# Shield.net
KiCad netlist of a schematic drawn in Altium Designer
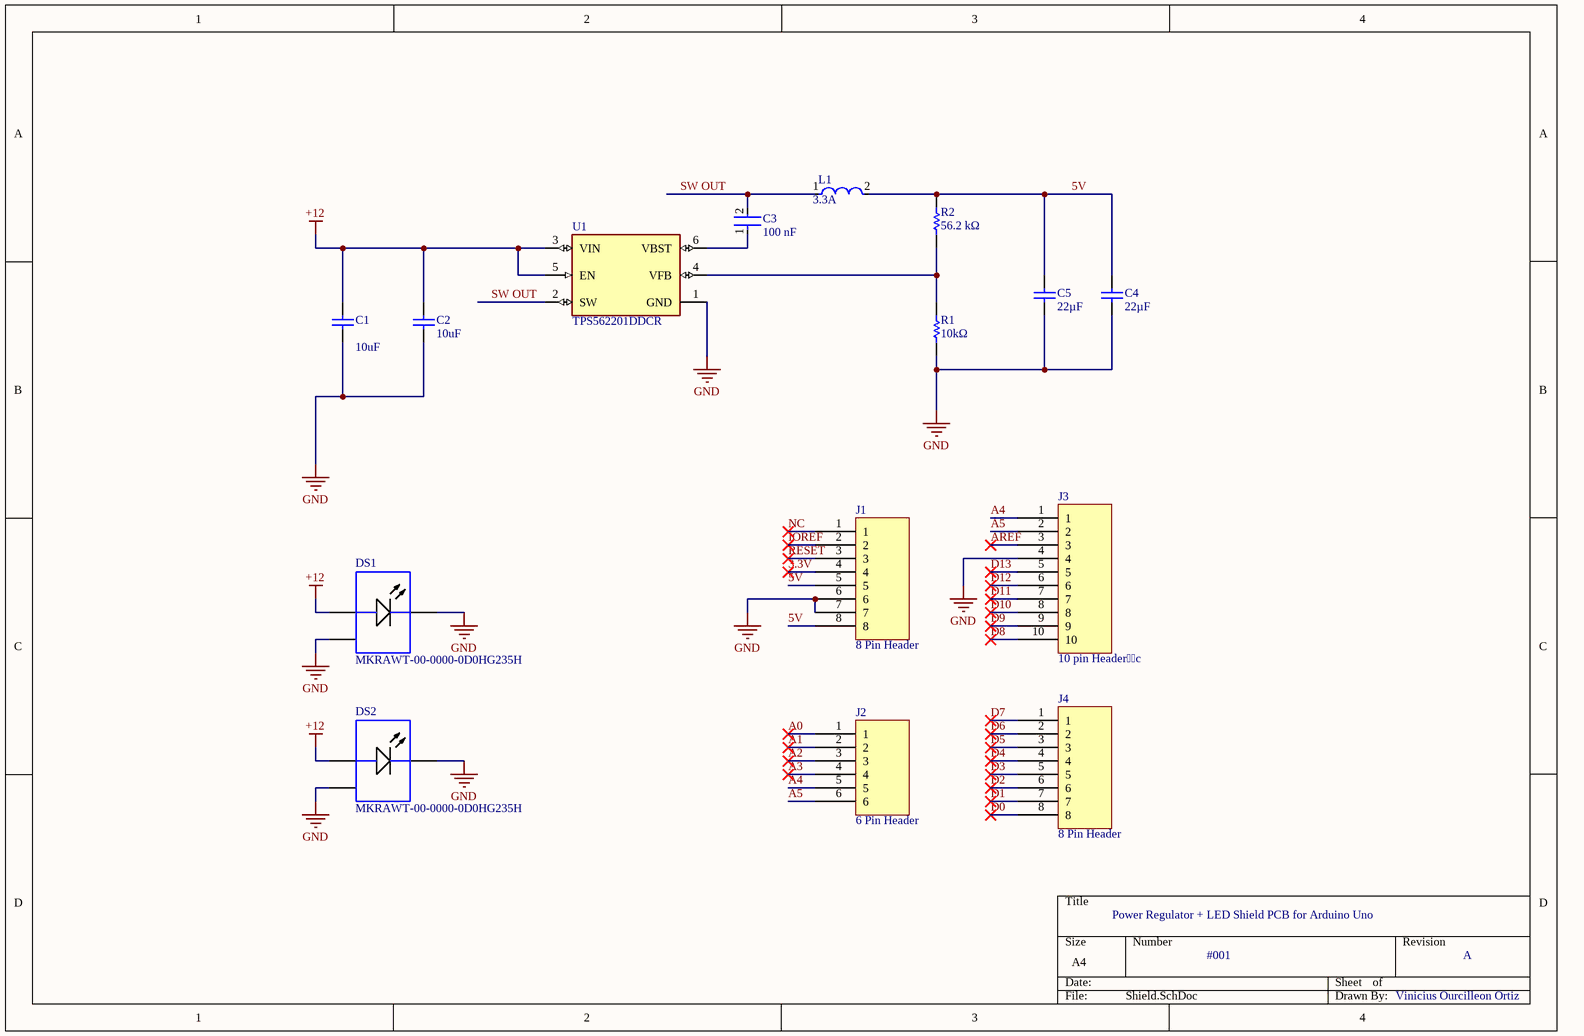
[diagram p0: Shield.SchDoc]

(export (version "E")
  (design (tool "Eeschema 10.0.6"))
  (components
    (comp (ref "C1")
      (value "GRM31CR61E106KA12L")
      (footprint "CAPC3216X180X55ML20T25")
      (description "Chip Capacitor, 10 uF, +/- 10%, 25 V, -55 to 85 degC, 1206 (3216 Metric), RoHS, Tape and Reel")
      (fields
        (field (name "MANUFACTURER") "Murata")
        (field (name "TOLERANCE") "10%")
        (field (name "CAPACITANCE") "10uF")
      )
      (libsource (lib "Altium Content Vault") (part "CAP-NP-2"))
    )
    (comp (ref "C2")
      (value "GRM31CR61E106KA12L")
      (footprint "CAPC3216X180X55ML20T25")
      (description "Chip Capacitor, 10 uF, +/- 10%, 25 V, -55 to 85 degC, 1206 (3216 Metric), RoHS, Tape and Reel")
      (fields
        (field (name "MANUFACTURER") "Murata")
        (field (name "TOLERANCE") "10%")
        (field (name "CAPACITANCE") "10uF")
      )
      (libsource (lib "Altium Content Vault") (part "CAP-NP-2"))
    )
    (comp (ref "C3")
      (value "CC0805KRX7R8BB104")
      (footprint "FP-CC0805-0_85-MFG")
      (description "CAP CER 0.1UF 25V X7R 0805")
      (fields
        (field (name "TOLERANCE") "0.1")
        (field (name "MANUFACTURER") "Yageo")
        (field (name "CAPACITANCE") "100 nF")
      )
      (libsource (lib "Altium Content Vault") (part "11868f565c42a9108669ba33697ecf6"))
    )
    (comp (ref "C4")
      (value "C1608X5R1A226M080AC")
      (footprint "CAPC1608X100X20ML10")
      (description "Chip Capacitor, 22 uF, +/- 20%, 10 V, -55 to 85 degC, 0603 (1608 Metric), RoHS, Tape and Reel")
      (fields
        (field (name "MANUFACTURER") "TDK")
        (field (name "TOLERANCE") "±20%")
        (field (name "CAPACITANCE") "22µF")
      )
      (libsource (lib "Altium Content Vault") (part "CAP-NP-2"))
    )
    (comp (ref "C5")
      (value "C1608X5R1A226M080AC")
      (footprint "CAPC1608X100X20ML10")
      (description "Chip Capacitor, 22 uF, +/- 20%, 10 V, -55 to 85 degC, 0603 (1608 Metric), RoHS, Tape and Reel")
      (fields
        (field (name "MANUFACTURER") "TDK")
        (field (name "TOLERANCE") "±20%")
        (field (name "CAPACITANCE") "22µF")
      )
      (libsource (lib "Altium Content Vault") (part "CAP-NP-2"))
    )
    (comp (ref "DS1")
      (value "MKRAWT-00-0000-0D0HG235H")
      (footprint "CREE-MK-R-2_V")
      (description "LED, White, 12 V, 2-Pin SMD, RoHS, Tape and Reel")
      (libsource (lib "Altium Content Vault") (part "LED_WHITE-3"))
    )
    (comp (ref "DS2")
      (value "MKRAWT-00-0000-0D0HG235H")
      (footprint "CREE-MK-R-2_V")
      (description "LED, White, 12 V, 2-Pin SMD, RoHS, Tape and Reel")
      (libsource (lib "Altium Content Vault") (part "LED_WHITE-3"))
    )
    (comp (ref "J1")
      (value "8 Pin Header")
      (footprint "SSQ-108-03-T-S-Footprint-1")
      (libsource (lib "HSRW") (part "SSQ-108-03-T-S-Symbol-1"))
    )
    (comp (ref "J2")
      (value "6 Pin Header")
      (footprint "SSQ-106-03-T-S-Footprint-1")
      (libsource (lib "HSRW") (part "SSQ-106-03-T-S-Symbol-1"))
    )
    (comp (ref "J3")
      (value "10 pin Headerc")
      (footprint "FP-SSQ-110-03-T-S-MFG")
      (libsource (lib "HSRW") (part "SSQ-110-03-T-S"))
    )
    (comp (ref "J4")
      (value "8 Pin Header")
      (footprint "SSQ-108-03-T-S-Footprint-1")
      (libsource (lib "HSRW") (part "SSQ-108-03-T-S-Symbol-1"))
    )
    (comp (ref "L1")
      (value "IHLP1212BZER3R3M11")
      (footprint "FP-IHLP-1212BZ-11-MFG")
      (description "FIXED IND 3.3UH 2.7A 61 MOHM SMD")
      (fields (field (name "SATURATION CURRENT") "3.3A") (field (name "TOLERANCE") "20%"))
      (libsource (lib "Altium Content Vault") (part "725321dda6339637d4d059423bc1c3c"))
    )
    (comp (ref "R1")
      (value "10kΩ")
      (footprint "RESC0603X28X15LL05T05")
      (fields (field (name "PART NUMBER") "CRCW020110K0FKED") (field (name "MANUFACTURER") "Vishay Dale"))
      (libsource (lib "Altium Content Vault") (part "RES"))
    )
    (comp (ref "R2")
      (value "56.2 kΩ")
      (footprint "RESC0603X28X15NL05T05")
      (fields (field (name "MANUFACTURER") "Vishay Dale") (field (name "PART NUMBER") "CRCW020156K2FKED"))
      (libsource (lib "Altium Content Vault") (part "RES"))
    )
    (comp (ref "U1")
      (value "TPS562201DDCR")
      (footprint "FP-DDC0006A-IPC_C")
      (description "IC REG BUCK ADJ 2A TSOT23-6")
      (libsource (lib "Altium Content Vault") (part "957e164956730ea4bf6293280af19fc"))
    )
  )
  (nets
    (net (code "1") (name "+12") (class "Default")
      (node (ref "C1") (pin "1") (pinfunction "1_1") (pintype "passive"))
      (node (ref "C2") (pin "1") (pinfunction "1_1") (pintype "passive"))
      (node (ref "DS1") (pin "1") (pinfunction "A_1") (pintype "passive"))
      (node (ref "DS2") (pin "1") (pinfunction "A_1") (pintype "passive"))
      (node (ref "U1") (pin "3") (pinfunction "VIN_3") (pintype "bidirectional"))
      (node (ref "U1") (pin "5") (pinfunction "EN_5") (pintype "input"))
    )
    (net (code "2") (name "/3.3V") (class "Default")
      (node (ref "J1") (pin "4") (pinfunction "4_4") (pintype "passive+no_connect"))
    )
    (net (code "3") (name "/5V") (class "Default")
      (node (ref "C4") (pin "1") (pinfunction "1_1") (pintype "passive"))
      (node (ref "C5") (pin "1") (pinfunction "1_1") (pintype "passive"))
      (node (ref "J1") (pin "5") (pinfunction "5_5") (pintype "passive"))
      (node (ref "J1") (pin "8") (pinfunction "8_8") (pintype "passive"))
      (node (ref "L1") (pin "2") (pinfunction "2_2") (pintype "passive"))
      (node (ref "R2") (pin "1") (pinfunction "1_1") (pintype "passive"))
    )
    (net (code "4") (name "/A0") (class "Default")
      (node (ref "J2") (pin "1") (pinfunction "1_1") (pintype "passive+no_connect"))
    )
    (net (code "5") (name "/A1") (class "Default")
      (node (ref "J2") (pin "2") (pinfunction "2_2") (pintype "passive+no_connect"))
    )
    (net (code "6") (name "/A2") (class "Default")
      (node (ref "J2") (pin "3") (pinfunction "3_3") (pintype "passive+no_connect"))
    )
    (net (code "7") (name "/A3") (class "Default")
      (node (ref "J2") (pin "4") (pinfunction "4_4") (pintype "passive+no_connect"))
    )
    (net (code "8") (name "/A4") (class "Default")
      (node (ref "J2") (pin "5") (pinfunction "5_5") (pintype "passive"))
      (node (ref "J3") (pin "1") (pinfunction "1_1") (pintype "passive"))
    )
    (net (code "9") (name "/A5") (class "Default")
      (node (ref "J2") (pin "6") (pinfunction "6_6") (pintype "passive"))
      (node (ref "J3") (pin "2") (pinfunction "2_2") (pintype "passive"))
    )
    (net (code "10") (name "/AREF") (class "Default")
      (node (ref "J3") (pin "3") (pinfunction "3_3") (pintype "passive+no_connect"))
    )
    (net (code "11") (name "/D0") (class "Default")
      (node (ref "J4") (pin "8") (pinfunction "8_8") (pintype "passive+no_connect"))
    )
    (net (code "12") (name "/D1") (class "Default")
      (node (ref "J4") (pin "7") (pinfunction "7_7") (pintype "passive+no_connect"))
    )
    (net (code "13") (name "/D2") (class "Default")
      (node (ref "J4") (pin "6") (pinfunction "6_6") (pintype "passive+no_connect"))
    )
    (net (code "14") (name "/D3") (class "Default")
      (node (ref "J4") (pin "5") (pinfunction "5_5") (pintype "passive+no_connect"))
    )
    (net (code "15") (name "/D4") (class "Default")
      (node (ref "J4") (pin "4") (pinfunction "4_4") (pintype "passive+no_connect"))
    )
    (net (code "16") (name "/D5") (class "Default")
      (node (ref "J4") (pin "3") (pinfunction "3_3") (pintype "passive+no_connect"))
    )
    (net (code "17") (name "/D6") (class "Default")
      (node (ref "J4") (pin "2") (pinfunction "2_2") (pintype "passive+no_connect"))
    )
    (net (code "18") (name "/D7") (class "Default")
      (node (ref "J4") (pin "1") (pinfunction "1_1") (pintype "passive+no_connect"))
    )
    (net (code "19") (name "/D8") (class "Default")
      (node (ref "J3") (pin "10") (pinfunction "10_10") (pintype "passive+no_connect"))
    )
    (net (code "20") (name "/D9") (class "Default")
      (node (ref "J3") (pin "9") (pinfunction "9_9") (pintype "passive+no_connect"))
    )
    (net (code "21") (name "/D10") (class "Default")
      (node (ref "J3") (pin "8") (pinfunction "8_8") (pintype "passive+no_connect"))
    )
    (net (code "22") (name "/D11") (class "Default")
      (node (ref "J3") (pin "7") (pinfunction "7_7") (pintype "passive+no_connect"))
    )
    (net (code "23") (name "/D12") (class "Default")
      (node (ref "J3") (pin "6") (pinfunction "6_6") (pintype "passive+no_connect"))
    )
    (net (code "24") (name "/D13") (class "Default")
      (node (ref "J3") (pin "5") (pinfunction "5_5") (pintype "passive+no_connect"))
    )
    (net (code "25") (name "/IOREF") (class "Default")
      (node (ref "J1") (pin "2") (pinfunction "2_2") (pintype "passive+no_connect"))
    )
    (net (code "26") (name "/NC") (class "Default")
      (node (ref "J1") (pin "1") (pinfunction "1_1") (pintype "passive+no_connect"))
    )
    (net (code "27") (name "/RESET") (class "Default")
      (node (ref "J1") (pin "3") (pinfunction "3_3") (pintype "passive+no_connect"))
    )
    (net (code "28") (name "/SW OUT") (class "Default")
      (node (ref "C3") (pin "2") (pinfunction "2_2") (pintype "passive"))
      (node (ref "L1") (pin "1") (pinfunction "1_1") (pintype "passive"))
      (node (ref "U1") (pin "2") (pinfunction "SW_2") (pintype "bidirectional"))
    )
    (net (code "29") (name "GND") (class "Default")
      (node (ref "C1") (pin "2") (pinfunction "2_2") (pintype "passive"))
      (node (ref "C2") (pin "2") (pinfunction "2_2") (pintype "passive"))
      (node (ref "C4") (pin "2") (pinfunction "2_2") (pintype "passive"))
      (node (ref "C5") (pin "2") (pinfunction "2_2") (pintype "passive"))
      (node (ref "DS1") (pin "2") (pinfunction "K_2") (pintype "passive"))
      (node (ref "DS1") (pin "3") (pinfunction "EP_3") (pintype "passive"))
      (node (ref "DS2") (pin "2") (pinfunction "K_2") (pintype "passive"))
      (node (ref "DS2") (pin "3") (pinfunction "EP_3") (pintype "passive"))
      (node (ref "J1") (pin "6") (pinfunction "6_6") (pintype "passive"))
      (node (ref "J1") (pin "7") (pinfunction "7_7") (pintype "passive"))
      (node (ref "J3") (pin "4") (pinfunction "4_4") (pintype "passive"))
      (node (ref "R1") (pin "2") (pinfunction "2_2") (pintype "passive"))
      (node (ref "U1") (pin "1") (pinfunction "GND_1") (pintype "power_in"))
    )
    (net (code "30") (name "Net-(U1-VBST)") (class "Default")
      (node (ref "C3") (pin "1") (pinfunction "1_1") (pintype "passive"))
      (node (ref "U1") (pin "6") (pinfunction "VBST_6") (pintype "bidirectional"))
    )
    (net (code "31") (name "Net-(U1-VFB)") (class "Default")
      (node (ref "R1") (pin "1") (pinfunction "1_1") (pintype "passive"))
      (node (ref "R2") (pin "2") (pinfunction "2_2") (pintype "passive"))
      (node (ref "U1") (pin "4") (pinfunction "VFB_4") (pintype "bidirectional"))
    )
  )
)
